# BleShield.net
KiCad netlist of a schematic drawn in EAGLE
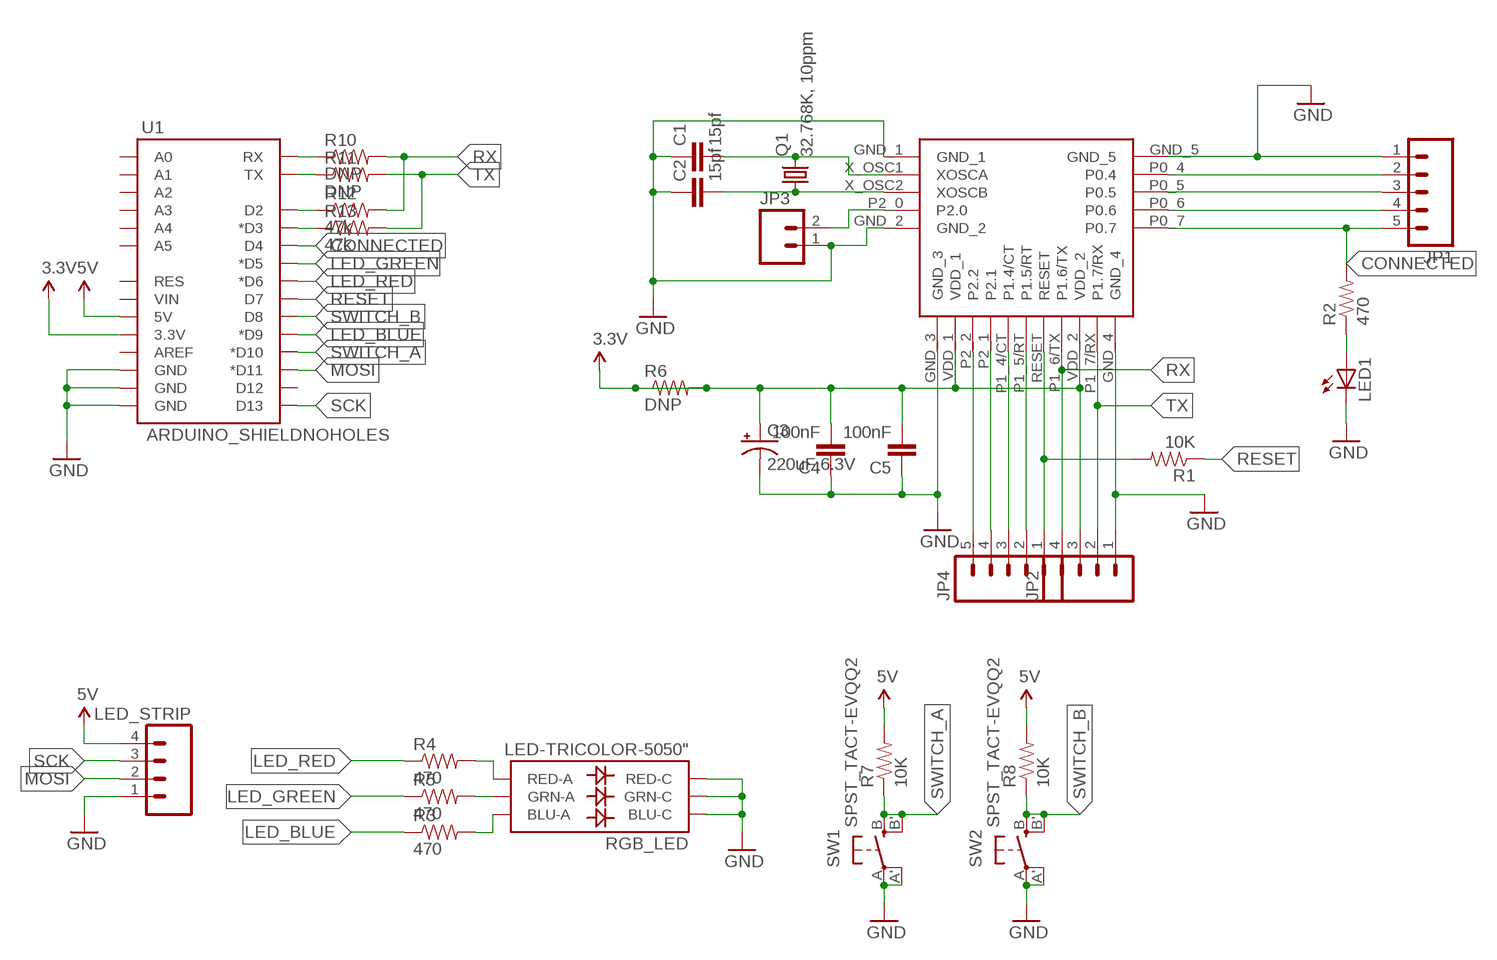
[diagram p0: schematic, sheet 1]

(export (version "E")
  (design (tool "Eeschema 10.0.6"))
  (components
    (comp (ref "C1")
      (value "15pf")
      (footprint "eagle-import:0805")
      (libsource (lib "eagle-import") (part "CAP0805"))
    )
    (comp (ref "C2")
      (value "15pf")
      (footprint "eagle-import:0805")
      (libsource (lib "eagle-import") (part "CAP0805"))
    )
    (comp (ref "C3")
      (value "220uF 6.3V")
      (footprint "eagle-import:C_6032-28R")
      (libsource (lib "eagle-import") (part "CPOL-USC/6032-28R"))
    )
    (comp (ref "C4")
      (value "100nF")
      (footprint "eagle-import:0805")
      (libsource (lib "eagle-import") (part "CAP0805"))
    )
    (comp (ref "C5")
      (value "100nF")
      (footprint "eagle-import:0805")
      (libsource (lib "eagle-import") (part "CAP0805"))
    )
    (comp (ref "JP1")
      (value "M051.27MM")
      (footprint "eagle-import:1X05-1.27MM")
      (libsource (lib "eagle-import") (part "M051.27MM"))
    )
    (comp (ref "JP2")
      (value "M041.27MM")
      (footprint "eagle-import:1X04-1.27MM")
      (libsource (lib "eagle-import") (part "M041.27MM"))
    )
    (comp (ref "JP3")
      (value "M02")
      (footprint "eagle-import:1X02-1.27MM")
      (libsource (lib "eagle-import") (part "M02"))
    )
    (comp (ref "JP4")
      (value "M051.27MM")
      (footprint "eagle-import:1X05-1.27MM")
      (libsource (lib "eagle-import") (part "M051.27MM"))
    )
    (comp (ref "LED1")
      (value "LEDCHIPLED_0805")
      (footprint "eagle-import:CHIPLED_0805")
      (libsource (lib "eagle-import") (part "LEDCHIPLED_0805"))
    )
    (comp (ref "LED_STRIP")
      (value "M04PTH")
      (footprint "eagle-import:1X04")
      (libsource (lib "eagle-import") (part "M04PTH"))
    )
    (comp (ref "Q1")
      (value "32.768K, 10ppm")
      (footprint "eagle-import:CRYSTAL_3215")
      (libsource (lib "eagle-import") (part "CRYSTAL3215"))
    )
    (comp (ref "R1")
      (value "10K")
      (footprint "eagle-import:0805")
      (libsource (lib "eagle-import") (part "RESISTOR0805-RES"))
    )
    (comp (ref "R2")
      (value "470")
      (footprint "eagle-import:0805")
      (libsource (lib "eagle-import") (part "RESISTOR0805-RES"))
    )
    (comp (ref "R3")
      (value "470")
      (footprint "eagle-import:0805")
      (libsource (lib "eagle-import") (part "RESISTOR0805-RES"))
    )
    (comp (ref "R4")
      (value "470")
      (footprint "eagle-import:0805")
      (libsource (lib "eagle-import") (part "RESISTOR0805-RES"))
    )
    (comp (ref "R5")
      (value "470")
      (footprint "eagle-import:0805")
      (libsource (lib "eagle-import") (part "RESISTOR0805-RES"))
    )
    (comp (ref "R6")
      (value "DNP")
      (footprint "eagle-import:0805")
      (libsource (lib "eagle-import") (part "RESISTOR0805-RES"))
    )
    (comp (ref "R7")
      (value "10K")
      (footprint "eagle-import:0805")
      (libsource (lib "eagle-import") (part "RESISTOR0805-RES"))
    )
    (comp (ref "R8")
      (value "10K")
      (footprint "eagle-import:0805")
      (libsource (lib "eagle-import") (part "RESISTOR0805-RES"))
    )
    (comp (ref "R10")
      (value "DNP")
      (footprint "eagle-import:0805")
      (libsource (lib "eagle-import") (part "RESISTOR0805-RES"))
    )
    (comp (ref "R11")
      (value "DNP")
      (footprint "eagle-import:0805")
      (libsource (lib "eagle-import") (part "RESISTOR0805-RES"))
    )
    (comp (ref "R12")
      (value "47k")
      (footprint "eagle-import:0805")
      (libsource (lib "eagle-import") (part "RESISTOR0805-RES"))
    )
    (comp (ref "R13")
      (value "47k")
      (footprint "eagle-import:0805")
      (libsource (lib "eagle-import") (part "RESISTOR0805-RES"))
    )
    (comp (ref "RGB_LED")
      (value "LED-TRICOLOR-5050\"")
      (footprint "eagle-import:LED-TRICOLOR-5050-FIXED")
      (libsource (lib "eagle-import") (part "LED-TRICOLOR-5050{dblquote}"))
    )
    (comp (ref "SW1")
      (value "SPST_TACT-EVQQ2")
      (footprint "eagle-import:EVQ-Q2")
      (libsource (lib "eagle-import") (part "SPST_TACT-EVQQ2"))
    )
    (comp (ref "SW2")
      (value "SPST_TACT-EVQQ2")
      (footprint "eagle-import:EVQ-Q2")
      (libsource (lib "eagle-import") (part "SPST_TACT-EVQQ2"))
    )
    (comp (ref "U$1")
      (value "BG213L")
      (footprint "eagle-import:BG312L")
      (libsource (lib "eagle-import") (part "BG213L"))
    )
    (comp (ref "U1")
      (value "ARDUINO_SHIELDNOHOLES")
      (footprint "eagle-import:DUEMILANOVE_SHIELD_NOHOLES")
      (libsource (lib "eagle-import") (part "ARDUINO_SHIELDNOHOLES"))
    )
  )
  (nets
    (net (code "1") (name "3.3V") (class "Default")
      (node (ref "C3") (pin "+") (pinfunction "+_+") (pintype "passive"))
      (node (ref "C4") (pin "2") (pinfunction "2_2") (pintype "passive"))
      (node (ref "C5") (pin "2") (pinfunction "2_2") (pintype "passive"))
      (node (ref "JP2") (pin "3") (pinfunction "3_3") (pintype "passive"))
      (node (ref "R6") (pin "1") (pinfunction "1_1") (pintype "passive"))
      (node (ref "R6") (pin "2") (pinfunction "2_2") (pintype "passive"))
      (node (ref "U$1") (pin "VDD_1") (pinfunction "VDD_1_VDD_1") (pintype "bidirectional"))
      (node (ref "U$1") (pin "VDD_2") (pinfunction "VDD_2_VDD_2") (pintype "bidirectional"))
      (node (ref "U1") (pin "3.3V") (pinfunction "3.3V_3.3V") (pintype "bidirectional"))
    )
    (net (code "2") (name "5V") (class "Default")
      (node (ref "LED_STRIP") (pin "4") (pinfunction "4_4") (pintype "passive"))
      (node (ref "R7") (pin "2") (pinfunction "2_2") (pintype "passive"))
      (node (ref "R8") (pin "2") (pinfunction "2_2") (pintype "passive"))
      (node (ref "U1") (pin "5V") (pinfunction "5V_5V") (pintype "bidirectional"))
    )
    (net (code "3") (name "CONNECTED") (class "Default")
      (node (ref "JP1") (pin "5") (pinfunction "5_5") (pintype "passive"))
      (node (ref "R2") (pin "2") (pinfunction "2_2") (pintype "passive"))
      (node (ref "U$1") (pin "P0_7") (pinfunction "P0.7_P0_7") (pintype "bidirectional"))
      (node (ref "U1") (pin "D4") (pinfunction "D4_D4") (pintype "bidirectional"))
    )
    (net (code "4") (name "GND") (class "Default")
      (node (ref "C1") (pin "1") (pinfunction "1_1") (pintype "passive"))
      (node (ref "C2") (pin "1") (pinfunction "1_1") (pintype "passive"))
      (node (ref "C3") (pin "-") (pinfunction "-_-") (pintype "passive"))
      (node (ref "C4") (pin "1") (pinfunction "1_1") (pintype "passive"))
      (node (ref "C5") (pin "1") (pinfunction "1_1") (pintype "passive"))
      (node (ref "JP1") (pin "1") (pinfunction "1_1") (pintype "passive"))
      (node (ref "JP2") (pin "1") (pinfunction "1_1") (pintype "passive"))
      (node (ref "JP3") (pin "1") (pinfunction "1_1") (pintype "passive"))
      (node (ref "LED1") (pin "C") (pinfunction "C_C") (pintype "passive"))
      (node (ref "LED_STRIP") (pin "1") (pinfunction "1_1") (pintype "passive"))
      (node (ref "RGB_LED") (pin "1") (pinfunction "BLU-C_1") (pintype "bidirectional"))
      (node (ref "RGB_LED") (pin "2") (pinfunction "RED-C_2") (pintype "bidirectional"))
      (node (ref "RGB_LED") (pin "3") (pinfunction "GRN-C_3") (pintype "bidirectional"))
      (node (ref "SW1") (pin "A") (pinfunction "P_A") (pintype "passive"))
      (node (ref "SW1") (pin "A'") (pinfunction "P1_A'") (pintype "passive"))
      (node (ref "SW2") (pin "A") (pinfunction "P_A") (pintype "passive"))
      (node (ref "SW2") (pin "A'") (pinfunction "P1_A'") (pintype "passive"))
      (node (ref "U$1") (pin "GND_1") (pinfunction "GND_1_GND_1") (pintype "bidirectional"))
      (node (ref "U$1") (pin "GND_2") (pinfunction "GND_2_GND_2") (pintype "bidirectional"))
      (node (ref "U$1") (pin "GND_3") (pinfunction "GND_3_GND_3") (pintype "bidirectional"))
      (node (ref "U$1") (pin "GND_4") (pinfunction "GND_4_GND_4") (pintype "bidirectional"))
      (node (ref "U$1") (pin "GND_5") (pinfunction "GND_5_GND_5") (pintype "bidirectional"))
      (node (ref "U1") (pin "GND@0") (pinfunction "GND_GND@0") (pintype "bidirectional"))
      (node (ref "U1") (pin "GND@1") (pinfunction "GND_GND@1") (pintype "bidirectional"))
      (node (ref "U1") (pin "GND@2") (pinfunction "GND_GND@2") (pintype "bidirectional"))
    )
    (net (code "5") (name "LED_BLUE") (class "Default")
      (node (ref "R3") (pin "1") (pinfunction "1_1") (pintype "passive"))
      (node (ref "U1") (pin "D9") (pinfunction "*D9_D9") (pintype "bidirectional"))
    )
    (net (code "6") (name "LED_GREEN") (class "Default")
      (node (ref "R5") (pin "1") (pinfunction "1_1") (pintype "passive"))
      (node (ref "U1") (pin "D5") (pinfunction "*D5_D5") (pintype "bidirectional"))
    )
    (net (code "7") (name "LED_RED") (class "Default")
      (node (ref "R4") (pin "1") (pinfunction "1_1") (pintype "passive"))
      (node (ref "U1") (pin "D6") (pinfunction "*D6_D6") (pintype "bidirectional"))
    )
    (net (code "8") (name "MOSI") (class "Default")
      (node (ref "LED_STRIP") (pin "2") (pinfunction "2_2") (pintype "passive"))
      (node (ref "U1") (pin "D11") (pinfunction "*D11_D11") (pintype "bidirectional"))
    )
    (net (code "9") (name "Net-(JP4-Pad1)") (class "Default")
      (node (ref "JP4") (pin "1") (pinfunction "1_1") (pintype "passive"))
      (node (ref "R1") (pin "2") (pinfunction "2_2") (pintype "passive"))
      (node (ref "U$1") (pin "RESET") (pinfunction "RESET_RESET") (pintype "bidirectional"))
    )
    (net (code "10") (name "Net-(LED1-PadA)") (class "Default")
      (node (ref "LED1") (pin "A") (pinfunction "A_A") (pintype "passive"))
      (node (ref "R2") (pin "1") (pinfunction "1_1") (pintype "passive"))
    )
    (net (code "11") (name "Net-(Q1-1)") (class "Default")
      (node (ref "C2") (pin "2") (pinfunction "2_2") (pintype "passive"))
      (node (ref "Q1") (pin "P$1") (pinfunction "1_P$1") (pintype "passive"))
      (node (ref "U$1") (pin "X_OSC2") (pinfunction "XOSCB_X_OSC2") (pintype "bidirectional"))
    )
    (net (code "12") (name "Net-(Q1-2)") (class "Default")
      (node (ref "C1") (pin "2") (pinfunction "2_2") (pintype "passive"))
      (node (ref "Q1") (pin "P$2") (pinfunction "2_P$2") (pintype "passive"))
      (node (ref "U$1") (pin "X_OSC1") (pinfunction "XOSCA_X_OSC1") (pintype "bidirectional"))
    )
    (net (code "13") (name "Net-(R10-Pad1)") (class "Default")
      (node (ref "R10") (pin "1") (pinfunction "1_1") (pintype "passive"))
      (node (ref "U1") (pin "RX") (pinfunction "RX_RX") (pintype "bidirectional"))
    )
    (net (code "14") (name "Net-(R11-Pad1)") (class "Default")
      (node (ref "R11") (pin "1") (pinfunction "1_1") (pintype "passive"))
      (node (ref "U1") (pin "TX") (pinfunction "TX_TX") (pintype "bidirectional"))
    )
    (net (code "15") (name "Net-(R12-Pad1)") (class "Default")
      (node (ref "R12") (pin "1") (pinfunction "1_1") (pintype "passive"))
      (node (ref "U1") (pin "D2") (pinfunction "D2_D2") (pintype "bidirectional"))
    )
    (net (code "16") (name "Net-(RGB_LED-BLU-A)") (class "Default")
      (node (ref "R3") (pin "2") (pinfunction "2_2") (pintype "passive"))
      (node (ref "RGB_LED") (pin "6") (pinfunction "BLU-A_6") (pintype "bidirectional"))
    )
    (net (code "17") (name "Net-(RGB_LED-GRN-A)") (class "Default")
      (node (ref "R5") (pin "2") (pinfunction "2_2") (pintype "passive"))
      (node (ref "RGB_LED") (pin "4") (pinfunction "GRN-A_4") (pintype "bidirectional"))
    )
    (net (code "18") (name "Net-(RGB_LED-RED-A)") (class "Default")
      (node (ref "R4") (pin "2") (pinfunction "2_2") (pintype "passive"))
      (node (ref "RGB_LED") (pin "5") (pinfunction "RED-A_5") (pintype "bidirectional"))
    )
    (net (code "19") (name "Net-(U$1-P0.4)") (class "Default")
      (node (ref "JP1") (pin "2") (pinfunction "2_2") (pintype "passive"))
      (node (ref "U$1") (pin "P0_4") (pinfunction "P0.4_P0_4") (pintype "bidirectional"))
    )
    (net (code "20") (name "Net-(U$1-P0.5)") (class "Default")
      (node (ref "JP1") (pin "3") (pinfunction "3_3") (pintype "passive"))
      (node (ref "U$1") (pin "P0_5") (pinfunction "P0.5_P0_5") (pintype "bidirectional"))
    )
    (net (code "21") (name "Net-(U$1-P0.6)") (class "Default")
      (node (ref "JP1") (pin "4") (pinfunction "4_4") (pintype "passive"))
      (node (ref "U$1") (pin "P0_6") (pinfunction "P0.6_P0_6") (pintype "bidirectional"))
    )
    (net (code "22") (name "Net-(U$1-P1.4{slash}CT)") (class "Default")
      (node (ref "JP4") (pin "3") (pinfunction "3_3") (pintype "passive"))
      (node (ref "U$1") (pin "P1_4/CT") (pinfunction "P1.4/CT_P1_4/CT") (pintype "bidirectional"))
    )
    (net (code "23") (name "Net-(U$1-P1.5{slash}RT)") (class "Default")
      (node (ref "JP4") (pin "2") (pinfunction "2_2") (pintype "passive"))
      (node (ref "U$1") (pin "P1_5/RT") (pinfunction "P1.5/RT_P1_5/RT") (pintype "bidirectional"))
    )
    (net (code "24") (name "Net-(U$1-P2.0)") (class "Default")
      (node (ref "JP3") (pin "2") (pinfunction "2_2") (pintype "passive"))
      (node (ref "U$1") (pin "P2_0") (pinfunction "P2.0_P2_0") (pintype "bidirectional"))
    )
    (net (code "25") (name "Net-(U$1-P2.1)") (class "Default")
      (node (ref "JP4") (pin "4") (pinfunction "4_4") (pintype "passive"))
      (node (ref "U$1") (pin "P2_1") (pinfunction "P2.1_P2_1") (pintype "bidirectional"))
    )
    (net (code "26") (name "Net-(U$1-P2.2)") (class "Default")
      (node (ref "JP4") (pin "5") (pinfunction "5_5") (pintype "passive"))
      (node (ref "U$1") (pin "P2_2") (pinfunction "P2.2_P2_2") (pintype "bidirectional"))
    )
    (net (code "27") (name "Net-(U1-*D3)") (class "Default")
      (node (ref "R13") (pin "1") (pinfunction "1_1") (pintype "passive"))
      (node (ref "U1") (pin "D3") (pinfunction "*D3_D3") (pintype "bidirectional"))
    )
    (net (code "28") (name "RESET") (class "Default")
      (node (ref "R1") (pin "1") (pinfunction "1_1") (pintype "passive"))
      (node (ref "U1") (pin "D7") (pinfunction "D7_D7") (pintype "bidirectional"))
    )
    (net (code "29") (name "RX") (class "Default")
      (node (ref "JP2") (pin "4") (pinfunction "4_4") (pintype "passive"))
      (node (ref "R10") (pin "2") (pinfunction "2_2") (pintype "passive"))
      (node (ref "R12") (pin "2") (pinfunction "2_2") (pintype "passive"))
      (node (ref "U$1") (pin "P1_6/TX") (pinfunction "P1.6/TX_P1_6/TX") (pintype "bidirectional"))
    )
    (net (code "30") (name "SCK") (class "Default")
      (node (ref "LED_STRIP") (pin "3") (pinfunction "3_3") (pintype "passive"))
      (node (ref "U1") (pin "D13") (pinfunction "D13_D13") (pintype "bidirectional"))
    )
    (net (code "31") (name "SWITCH_A") (class "Default")
      (node (ref "R7") (pin "1") (pinfunction "1_1") (pintype "passive"))
      (node (ref "SW1") (pin "B") (pinfunction "S_B") (pintype "passive"))
      (node (ref "SW1") (pin "B'") (pinfunction "S1_B'") (pintype "passive"))
      (node (ref "U1") (pin "D10") (pinfunction "*D10_D10") (pintype "bidirectional"))
    )
    (net (code "32") (name "SWITCH_B") (class "Default")
      (node (ref "R8") (pin "1") (pinfunction "1_1") (pintype "passive"))
      (node (ref "SW2") (pin "B") (pinfunction "S_B") (pintype "passive"))
      (node (ref "SW2") (pin "B'") (pinfunction "S1_B'") (pintype "passive"))
      (node (ref "U1") (pin "D8") (pinfunction "D8_D8") (pintype "bidirectional"))
    )
    (net (code "33") (name "TX") (class "Default")
      (node (ref "JP2") (pin "2") (pinfunction "2_2") (pintype "passive"))
      (node (ref "R11") (pin "2") (pinfunction "2_2") (pintype "passive"))
      (node (ref "R13") (pin "2") (pinfunction "2_2") (pintype "passive"))
      (node (ref "U$1") (pin "P1_7/RX") (pinfunction "P1.7/RX_P1_7/RX") (pintype "bidirectional"))
    )
    (net (code "34") (name "unconnected-(U1-PadA0)") (class "Default")
      (node (ref "U1") (pin "A0") (pinfunction "A0_A0") (pintype "bidirectional"))
    )
    (net (code "35") (name "unconnected-(U1-PadA1)") (class "Default")
      (node (ref "U1") (pin "A1") (pinfunction "A1_A1") (pintype "bidirectional"))
    )
    (net (code "36") (name "unconnected-(U1-PadA2)") (class "Default")
      (node (ref "U1") (pin "A2") (pinfunction "A2_A2") (pintype "bidirectional"))
    )
    (net (code "37") (name "unconnected-(U1-PadA3)") (class "Default")
      (node (ref "U1") (pin "A3") (pinfunction "A3_A3") (pintype "bidirectional"))
    )
    (net (code "38") (name "unconnected-(U1-PadA4)") (class "Default")
      (node (ref "U1") (pin "A4") (pinfunction "A4_A4") (pintype "bidirectional"))
    )
    (net (code "39") (name "unconnected-(U1-PadA5)") (class "Default")
      (node (ref "U1") (pin "A5") (pinfunction "A5_A5") (pintype "bidirectional"))
    )
    (net (code "40") (name "unconnected-(U1-PadAREF)") (class "Default")
      (node (ref "U1") (pin "AREF") (pinfunction "AREF_AREF") (pintype "bidirectional"))
    )
    (net (code "41") (name "unconnected-(U1-PadD12)") (class "Default")
      (node (ref "U1") (pin "D12") (pinfunction "D12_D12") (pintype "bidirectional"))
    )
    (net (code "42") (name "unconnected-(U1-PadRES)") (class "Default")
      (node (ref "U1") (pin "RES") (pinfunction "RES_RES") (pintype "bidirectional"))
    )
    (net (code "43") (name "unconnected-(U1-PadVIN)") (class "Default")
      (node (ref "U1") (pin "VIN") (pinfunction "VIN_VIN") (pintype "bidirectional"))
    )
  )
)
